# USB_Interlock_V2.net
KiCad netlist of a schematic drawn in EAGLE
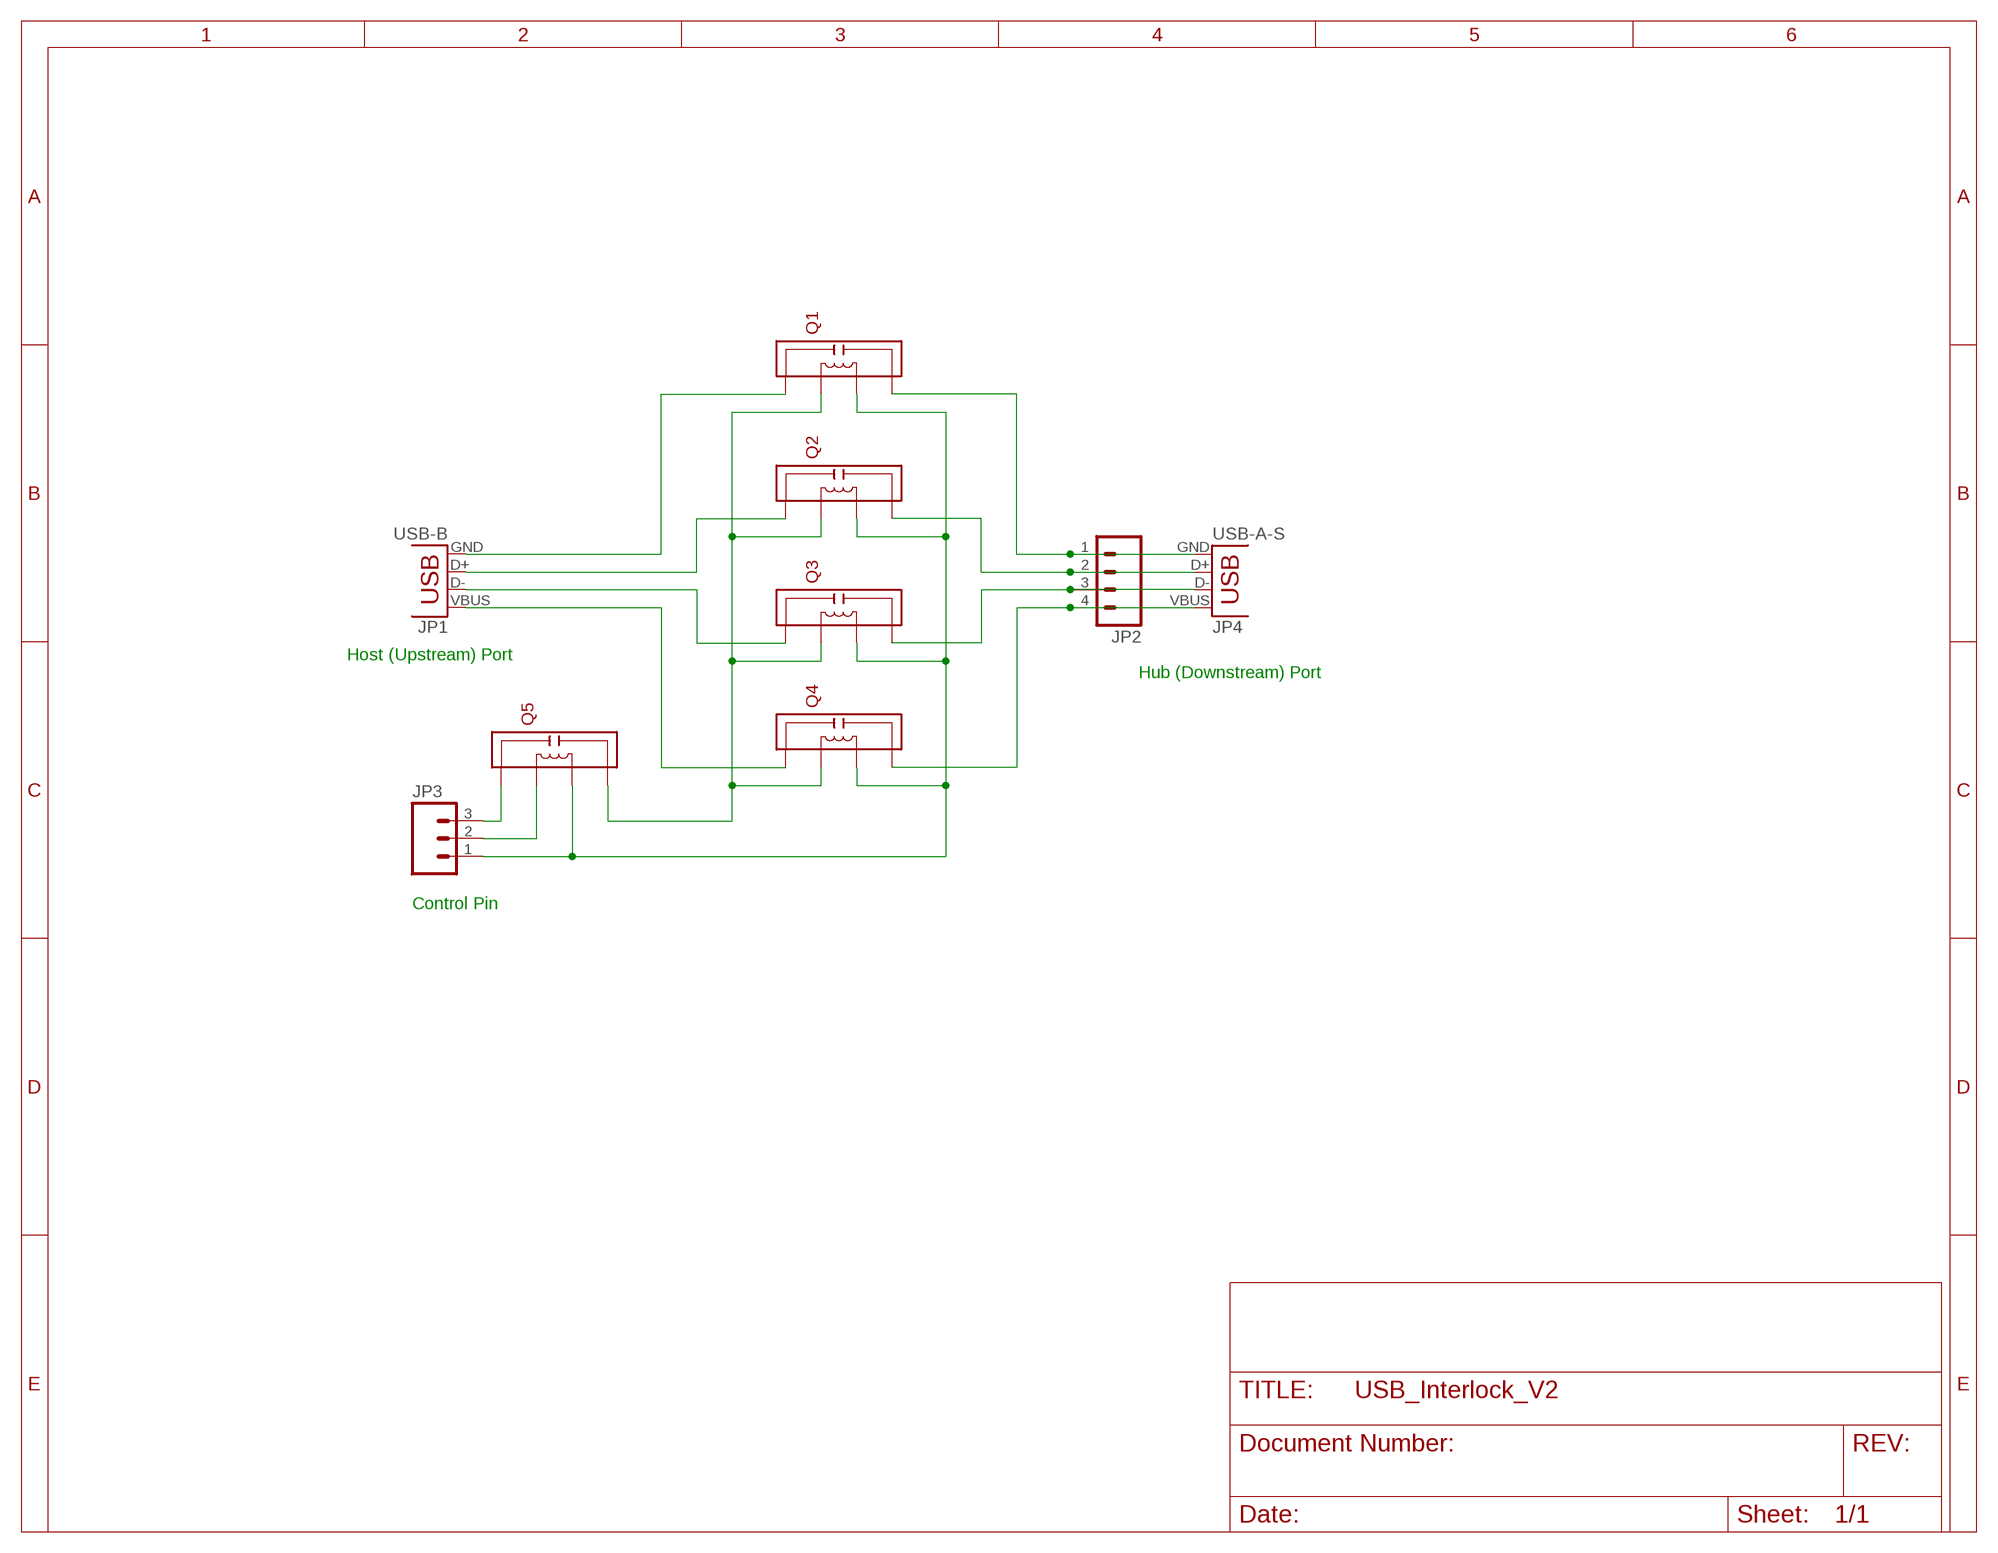
[diagram p0: schematic, sheet 1]

(export (version "E")
  (design (tool "Eeschema 10.0.6"))
  (components
    (comp (ref "JP1")
      (value "USB-B")
      (footprint "eagle-import:USB-B-PTH")
      (libsource (lib "eagle-import") (part "USBPTH"))
    )
    (comp (ref "JP2")
      (value "M04LONGPADS")
      (footprint "eagle-import:1X04_LONGPADS")
      (libsource (lib "eagle-import") (part "M04LONGPADS"))
    )
    (comp (ref "JP3")
      (value "M03LONGPADS")
      (footprint "eagle-import:1X03_LONGPADS")
      (libsource (lib "eagle-import") (part "M03LONGPADS"))
    )
    (comp (ref "JP4")
      (value "USB-A-S")
      (footprint "eagle-import:USB-A-S")
      (libsource (lib "eagle-import") (part "USB-A-S"))
    )
    (comp (ref "Q1")
      (value "9007-12-01")
      (footprint "eagle-import:9007-12-01")
      (libsource (lib "eagle-import") (part "9007-12-01"))
    )
    (comp (ref "Q2")
      (value "9007-12-01")
      (footprint "eagle-import:9007-12-01")
      (libsource (lib "eagle-import") (part "9007-12-01"))
    )
    (comp (ref "Q3")
      (value "9007-12-01")
      (footprint "eagle-import:9007-12-01")
      (libsource (lib "eagle-import") (part "9007-12-01"))
    )
    (comp (ref "Q4")
      (value "9007-12-01")
      (footprint "eagle-import:9007-12-01")
      (libsource (lib "eagle-import") (part "9007-12-01"))
    )
    (comp (ref "Q5")
      (value "9007-12-01")
      (footprint "eagle-import:9007-12-01")
      (libsource (lib "eagle-import") (part "9007-12-01"))
    )
  )
  (nets
    (net (code "1") (name "Net-(JP1-PadD+)") (class "Default")
      (node (ref "JP1") (pin "D+") (pinfunction "D+_D+") (pintype "bidirectional"))
      (node (ref "Q2") (pin "P$1") (pinfunction "P$1_P$1") (pintype "bidirectional"))
    )
    (net (code "2") (name "Net-(JP1-PadD-)") (class "Default")
      (node (ref "JP1") (pin "D-") (pinfunction "D-_D-") (pintype "bidirectional"))
      (node (ref "Q3") (pin "P$1") (pinfunction "P$1_P$1") (pintype "bidirectional"))
    )
    (net (code "3") (name "Net-(JP1-PadGND)") (class "Default")
      (node (ref "JP1") (pin "GND") (pinfunction "GND_GND") (pintype "bidirectional"))
      (node (ref "Q1") (pin "P$1") (pinfunction "P$1_P$1") (pintype "bidirectional"))
    )
    (net (code "4") (name "Net-(JP1-PadVBUS)") (class "Default")
      (node (ref "JP1") (pin "VBUS") (pinfunction "VBUS_VBUS") (pintype "bidirectional"))
      (node (ref "Q4") (pin "P$1") (pinfunction "P$1_P$1") (pintype "bidirectional"))
    )
    (net (code "5") (name "Net-(JP2-Pad1)") (class "Default")
      (node (ref "JP2") (pin "1") (pinfunction "1_1") (pintype "passive"))
      (node (ref "JP4") (pin "GND") (pinfunction "GND_GND") (pintype "bidirectional"))
      (node (ref "Q1") (pin "P$4") (pinfunction "P$4_P$4") (pintype "bidirectional"))
    )
    (net (code "6") (name "Net-(JP2-Pad2)") (class "Default")
      (node (ref "JP2") (pin "2") (pinfunction "2_2") (pintype "passive"))
      (node (ref "JP4") (pin "D+") (pinfunction "D+_D+") (pintype "bidirectional"))
      (node (ref "Q2") (pin "P$4") (pinfunction "P$4_P$4") (pintype "bidirectional"))
    )
    (net (code "7") (name "Net-(JP2-Pad3)") (class "Default")
      (node (ref "JP2") (pin "3") (pinfunction "3_3") (pintype "passive"))
      (node (ref "JP4") (pin "D-") (pinfunction "D-_D-") (pintype "bidirectional"))
      (node (ref "Q3") (pin "P$4") (pinfunction "P$4_P$4") (pintype "bidirectional"))
    )
    (net (code "8") (name "Net-(JP2-Pad4)") (class "Default")
      (node (ref "JP2") (pin "4") (pinfunction "4_4") (pintype "passive"))
      (node (ref "JP4") (pin "VBUS") (pinfunction "VBUS_VBUS") (pintype "bidirectional"))
      (node (ref "Q4") (pin "P$4") (pinfunction "P$4_P$4") (pintype "bidirectional"))
    )
    (net (code "9") (name "Net-(JP3-Pad1)") (class "Default")
      (node (ref "JP3") (pin "1") (pinfunction "1_1") (pintype "passive"))
      (node (ref "Q1") (pin "P$3") (pinfunction "P$3_P$3") (pintype "output"))
      (node (ref "Q2") (pin "P$3") (pinfunction "P$3_P$3") (pintype "output"))
      (node (ref "Q3") (pin "P$3") (pinfunction "P$3_P$3") (pintype "output"))
      (node (ref "Q4") (pin "P$3") (pinfunction "P$3_P$3") (pintype "output"))
      (node (ref "Q5") (pin "P$3") (pinfunction "P$3_P$3") (pintype "output"))
    )
    (net (code "10") (name "Net-(JP3-Pad2)") (class "Default")
      (node (ref "JP3") (pin "2") (pinfunction "2_2") (pintype "passive"))
      (node (ref "Q5") (pin "P$2") (pinfunction "P$2_P$2") (pintype "input"))
    )
    (net (code "11") (name "Net-(JP3-Pad3)") (class "Default")
      (node (ref "JP3") (pin "3") (pinfunction "3_3") (pintype "passive"))
      (node (ref "Q5") (pin "P$1") (pinfunction "P$1_P$1") (pintype "bidirectional"))
    )
    (net (code "12") (name "Net-(Q1-PadP$2)") (class "Default")
      (node (ref "Q1") (pin "P$2") (pinfunction "P$2_P$2") (pintype "input"))
      (node (ref "Q2") (pin "P$2") (pinfunction "P$2_P$2") (pintype "input"))
      (node (ref "Q3") (pin "P$2") (pinfunction "P$2_P$2") (pintype "input"))
      (node (ref "Q4") (pin "P$2") (pinfunction "P$2_P$2") (pintype "input"))
      (node (ref "Q5") (pin "P$4") (pinfunction "P$4_P$4") (pintype "bidirectional"))
    )
  )
)
